# BuckConverter.net
KiCad netlist of a schematic drawn in EAGLE
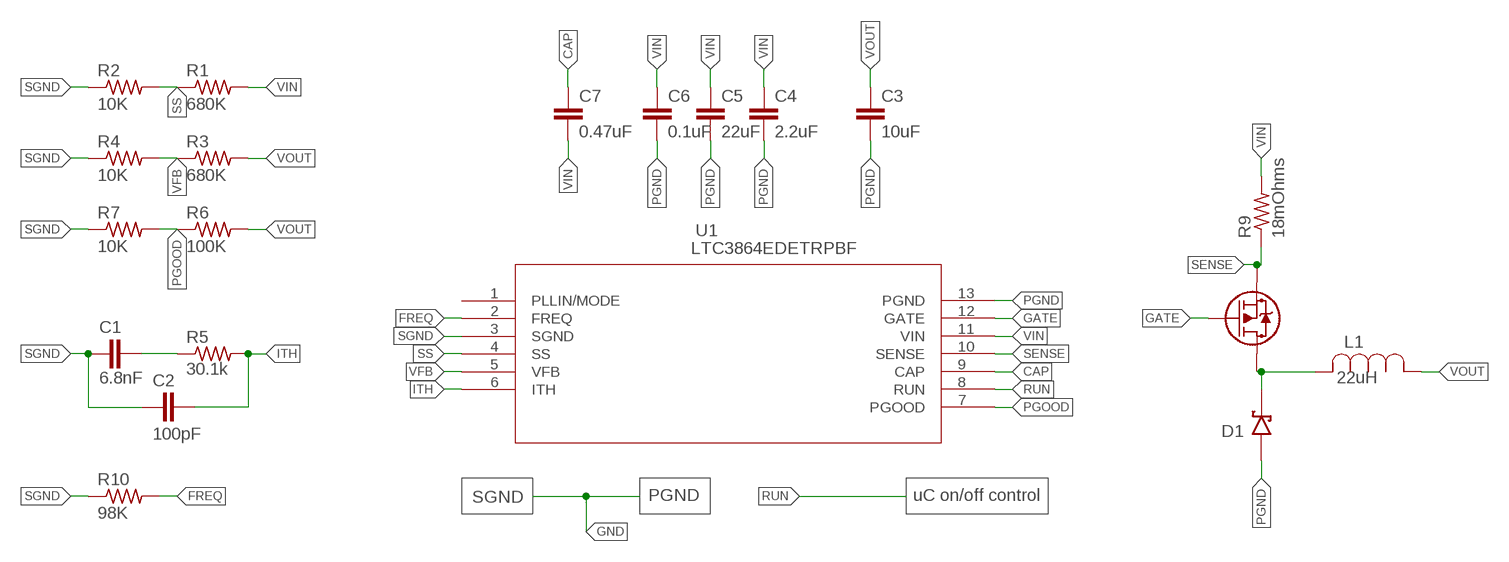
[diagram p0: schematic, sheet 1]

(export (version "E")
  (design (tool "Eeschema 10.0.6"))
  (components
    (comp (ref "C1")
      (value "6.8nF")
      (footprint "eagle-import:0805")
      (libsource (lib "eagle-import") (part "2.2UF-0805-25V-(+80/-20%)"))
    )
    (comp (ref "C2")
      (value "100pF")
      (footprint "eagle-import:0805")
      (libsource (lib "eagle-import") (part "2.2UF-0805-25V-(+80/-20%)"))
    )
    (comp (ref "C3")
      (value "10uF")
      (footprint "eagle-import:0805")
      (libsource (lib "eagle-import") (part "2.2UF-0805-25V-(+80/-20%)"))
    )
    (comp (ref "C4")
      (value "2.2uF")
      (footprint "eagle-import:0805")
      (libsource (lib "eagle-import") (part "2.2UF-0805-25V-(+80/-20%)"))
    )
    (comp (ref "C5")
      (value "22uF")
      (footprint "eagle-import:0805")
      (libsource (lib "eagle-import") (part "2.2UF-0805-25V-(+80/-20%)"))
    )
    (comp (ref "C6")
      (value "0.1uF")
      (footprint "eagle-import:0805")
      (libsource (lib "eagle-import") (part "2.2UF-0805-25V-(+80/-20%)"))
    )
    (comp (ref "C7")
      (value "0.47uF")
      (footprint "eagle-import:0805")
      (libsource (lib "eagle-import") (part "2.2UF-0805-25V-(+80/-20%)"))
    )
    (comp (ref "D1")
      (value "MBR1560STR")
      (footprint "eagle-import:DIO_MBR1560STR")
      (fields (field (name "MF") "SMC Diode Solutions"))
      (libsource (lib "eagle-import") (part "MBR1560STR"))
    )
    (comp (ref "L1")
      (value "22uH")
      (footprint "eagle-import:IND_IHLP-4040DZ_VIS")
      (fields
        (field (name "MANUFACTURER_PART_NUMBER") "IHLP4040DZER6R8M01")
        (field (name "COPYRIGHT") "Copyright (C) 2022 Ultra Librarian. All rights reserved.")
      )
      (libsource (lib "eagle-import") (part "IHLP4040DZER6R8M01"))
    )
    (comp (ref "R1")
      (value "680K")
      (footprint "eagle-import:M0805")
      (libsource (lib "eagle-import") (part "R-US_M0805"))
    )
    (comp (ref "R2")
      (value "10K")
      (footprint "eagle-import:M0805")
      (libsource (lib "eagle-import") (part "R-US_M0805"))
    )
    (comp (ref "R3")
      (value "680K")
      (footprint "eagle-import:M0805")
      (libsource (lib "eagle-import") (part "R-US_M0805"))
    )
    (comp (ref "R4")
      (value "10K")
      (footprint "eagle-import:M0805")
      (libsource (lib "eagle-import") (part "R-US_M0805"))
    )
    (comp (ref "R5")
      (value "30.1k")
      (footprint "eagle-import:M0805")
      (libsource (lib "eagle-import") (part "R-US_M0805"))
    )
    (comp (ref "R6")
      (value "100K")
      (footprint "eagle-import:M0805")
      (libsource (lib "eagle-import") (part "R-US_M0805"))
    )
    (comp (ref "R7")
      (value "10K")
      (footprint "eagle-import:M0805")
      (libsource (lib "eagle-import") (part "R-US_M0805"))
    )
    (comp (ref "R8")
      (value "RSJ250P10TL")
      (footprint "eagle-import:TRANS_R5009FNJ_ROM")
      (fields (field (name "COPYRIGHT") "Copyright (C) 2022 Ultra Librarian. All rights reserved."))
      (libsource (lib "eagle-import") (part "RSJ250P10TL"))
    )
    (comp (ref "R9")
      (value "18mOhms")
      (footprint "eagle-import:M0805")
      (libsource (lib "eagle-import") (part "R-US_M0805"))
    )
    (comp (ref "R10")
      (value "98K")
      (footprint "eagle-import:M0805")
      (libsource (lib "eagle-import") (part "R-US_M0805"))
    )
    (comp (ref "U1")
      (value "LTC3864EDETRPBF")
      (footprint "eagle-import:DFN-12_DE")
      (fields
        (field (name "DIGI-KEY_PART_NUMBER") "161-LTC3864EDE#TRPBFTR-ND")
        (field (name "MF") "Analog Devices")
        (field (name "MP") "LTC3864EDE#TRPBF")
      )
      (libsource (lib "eagle-import") (part "LTC3864EDETRPBF"))
    )
  )
  (nets
    (net (code "1") (name "CAP") (class "Default")
      (node (ref "C7") (pin "1") (pinfunction "1_1") (pintype "passive"))
      (node (ref "U1") (pin "9") (pinfunction "CAP_9") (pintype "passive"))
    )
    (net (code "2") (name "FREQ") (class "Default")
      (node (ref "R10") (pin "2") (pinfunction "2_2") (pintype "passive"))
      (node (ref "U1") (pin "2") (pinfunction "FREQ_2") (pintype "input"))
    )
    (net (code "3") (name "GATE") (class "Default")
      (node (ref "R8") (pin "1") (pinfunction "1_1") (pintype "passive"))
      (node (ref "U1") (pin "12") (pinfunction "GATE_12") (pintype "output"))
    )
    (net (code "5") (name "ITH") (class "Default")
      (node (ref "C2") (pin "2") (pinfunction "2_2") (pintype "passive"))
      (node (ref "R5") (pin "2") (pinfunction "2_2") (pintype "passive"))
      (node (ref "U1") (pin "6") (pinfunction "ITH_6") (pintype "output"))
    )
    (net (code "6") (name "Net-(C1-Pad2)") (class "Default")
      (node (ref "C1") (pin "2") (pinfunction "2_2") (pintype "passive"))
      (node (ref "R5") (pin "1") (pinfunction "1_1") (pintype "passive"))
    )
    (net (code "7") (name "Net-(R8-3)") (class "Default")
      (node (ref "D1") (pin "3") (pinfunction "K_3") (pintype "passive"))
      (node (ref "D1") (pin "4") (pinfunction "K_4") (pintype "passive"))
      (node (ref "L1") (pin "2") (pinfunction "2_2") (pintype "passive"))
      (node (ref "R8") (pin "2") (pinfunction "3_2") (pintype "passive"))
    )
    (net (code "8") (name "PGND") (class "Default")
      (node (ref "C3") (pin "2") (pinfunction "2_2") (pintype "passive"))
      (node (ref "C4") (pin "2") (pinfunction "2_2") (pintype "passive"))
      (node (ref "C5") (pin "2") (pinfunction "2_2") (pintype "passive"))
      (node (ref "C6") (pin "2") (pinfunction "2_2") (pintype "passive"))
      (node (ref "D1") (pin "1") (pinfunction "A_1") (pintype "passive"))
      (node (ref "D1") (pin "2") (pinfunction "A_2") (pintype "passive"))
      (node (ref "U1") (pin "13") (pinfunction "PGND_13") (pintype "power_in"))
    )
    (net (code "9") (name "PGOOD") (class "Default")
      (node (ref "R6") (pin "1") (pinfunction "1_1") (pintype "passive"))
      (node (ref "R7") (pin "2") (pinfunction "2_2") (pintype "passive"))
      (node (ref "U1") (pin "7") (pinfunction "PGOOD_7") (pintype "output"))
    )
    (net (code "10") (name "RUN") (class "Default")
      (node (ref "U1") (pin "8") (pinfunction "RUN_8") (pintype "input"))
    )
    (net (code "11") (name "SENSE") (class "Default")
      (node (ref "R8") (pin "3") (pinfunction "2_3") (pintype "passive"))
      (node (ref "R9") (pin "1") (pinfunction "1_1") (pintype "passive"))
      (node (ref "U1") (pin "10") (pinfunction "SENSE_10") (pintype "input"))
    )
    (net (code "12") (name "SGND") (class "Default")
      (node (ref "C1") (pin "1") (pinfunction "1_1") (pintype "passive"))
      (node (ref "C2") (pin "1") (pinfunction "1_1") (pintype "passive"))
      (node (ref "R10") (pin "1") (pinfunction "1_1") (pintype "passive"))
      (node (ref "R2") (pin "1") (pinfunction "1_1") (pintype "passive"))
      (node (ref "R4") (pin "1") (pinfunction "1_1") (pintype "passive"))
      (node (ref "R7") (pin "1") (pinfunction "1_1") (pintype "passive"))
      (node (ref "U1") (pin "3") (pinfunction "SGND_3") (pintype "power_in"))
    )
    (net (code "13") (name "SS") (class "Default")
      (node (ref "R1") (pin "1") (pinfunction "1_1") (pintype "passive"))
      (node (ref "R2") (pin "2") (pinfunction "2_2") (pintype "passive"))
      (node (ref "U1") (pin "4") (pinfunction "SS_4") (pintype "input"))
    )
    (net (code "14") (name "VFB") (class "Default")
      (node (ref "R3") (pin "1") (pinfunction "1_1") (pintype "passive"))
      (node (ref "R4") (pin "2") (pinfunction "2_2") (pintype "passive"))
      (node (ref "U1") (pin "5") (pinfunction "VFB_5") (pintype "output"))
    )
    (net (code "15") (name "VIN") (class "Default")
      (node (ref "C4") (pin "1") (pinfunction "1_1") (pintype "passive"))
      (node (ref "C5") (pin "1") (pinfunction "1_1") (pintype "passive"))
      (node (ref "C6") (pin "1") (pinfunction "1_1") (pintype "passive"))
      (node (ref "C7") (pin "2") (pinfunction "2_2") (pintype "passive"))
      (node (ref "R1") (pin "2") (pinfunction "2_2") (pintype "passive"))
      (node (ref "R9") (pin "2") (pinfunction "2_2") (pintype "passive"))
      (node (ref "U1") (pin "11") (pinfunction "VIN_11") (pintype "input"))
    )
    (net (code "16") (name "VOUT") (class "Default")
      (node (ref "C3") (pin "1") (pinfunction "1_1") (pintype "passive"))
      (node (ref "L1") (pin "1") (pinfunction "1_1") (pintype "passive"))
      (node (ref "R3") (pin "2") (pinfunction "2_2") (pintype "passive"))
      (node (ref "R6") (pin "2") (pinfunction "2_2") (pintype "passive"))
    )
    (net (code "17") (name "unconnected-(U1-PLLIN{slash}MODE-Pad1)") (class "Default")
      (node (ref "U1") (pin "1") (pinfunction "PLLIN/MODE_1") (pintype "input"))
    )
  )
)
